# SCH_8_MCP23017_IC_SS_2021-10-13.net
KiCad netlist of a schematic drawn in EasyEDA
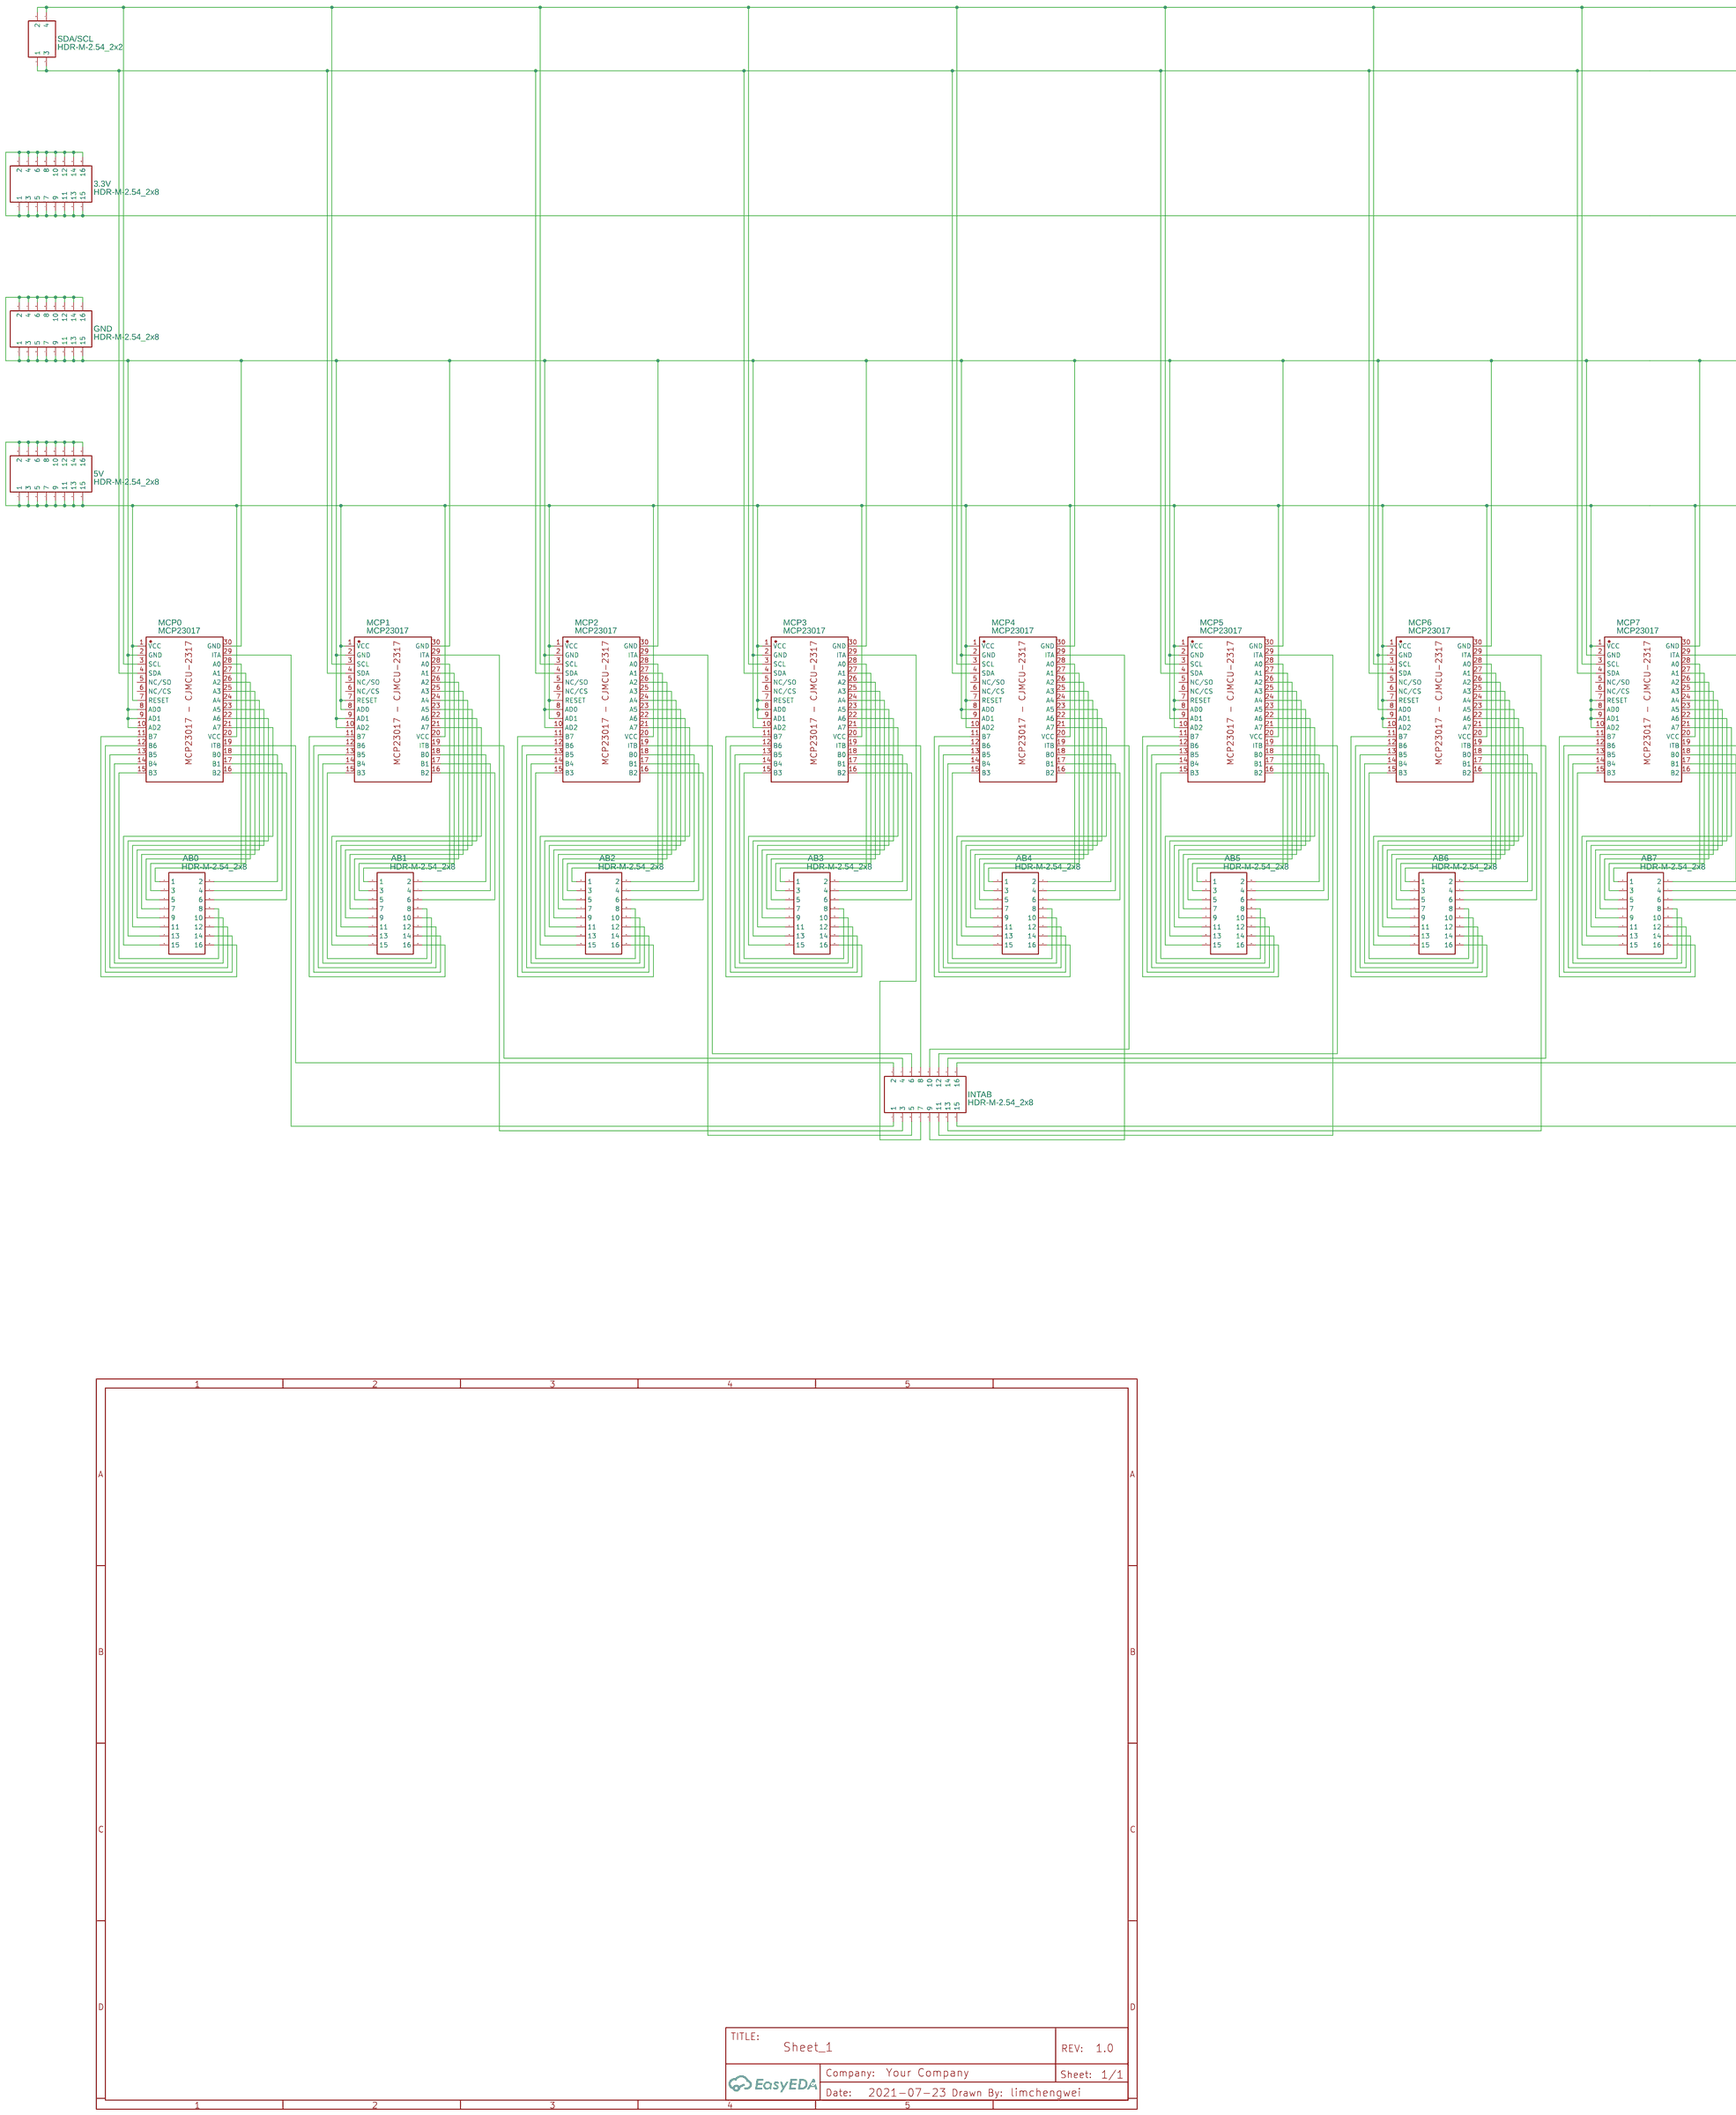
[diagram p0: schematic sheet]

(export (version "E")
  (design (tool "Eeschema 10.0.6"))
  (components
    (comp (ref "3.3V")
      (value "HDR-M-2.54_2x8")
      (fields (field (name "BOM_Supplier Part") "C68234"))
      (libsource (lib "") (part "HDR-M-2.54_2x8_2"))
    )
    (comp (ref "5V")
      (value "HDR-M-2.54_2x8")
      (fields (field (name "BOM_Supplier Part") "C68234"))
      (libsource (lib "") (part "HDR-M-2.54_2x8_3"))
    )
    (comp (ref "AB0")
      (value "HDR-M-2.54_2x8")
      (fields (field (name "BOM_Supplier Part") "C68234"))
      (libsource (lib "") (part "HDR-M-2.54_2x8"))
    )
    (comp (ref "AB1")
      (value "HDR-M-2.54_2x8")
      (fields (field (name "BOM_Supplier Part") "C68234"))
      (libsource (lib "") (part "HDR-M-2.54_2x8"))
    )
    (comp (ref "AB2")
      (value "HDR-M-2.54_2x8")
      (fields (field (name "BOM_Supplier Part") "C68234"))
      (libsource (lib "") (part "HDR-M-2.54_2x8"))
    )
    (comp (ref "AB3")
      (value "HDR-M-2.54_2x8")
      (fields (field (name "BOM_Supplier Part") "C68234"))
      (libsource (lib "") (part "HDR-M-2.54_2x8"))
    )
    (comp (ref "AB4")
      (value "HDR-M-2.54_2x8")
      (fields (field (name "BOM_Supplier Part") "C68234"))
      (libsource (lib "") (part "HDR-M-2.54_2x8"))
    )
    (comp (ref "AB5")
      (value "HDR-M-2.54_2x8")
      (fields (field (name "BOM_Supplier Part") "C68234"))
      (libsource (lib "") (part "HDR-M-2.54_2x8"))
    )
    (comp (ref "AB6")
      (value "HDR-M-2.54_2x8")
      (fields (field (name "BOM_Supplier Part") "C68234"))
      (libsource (lib "") (part "HDR-M-2.54_2x8"))
    )
    (comp (ref "AB7")
      (value "HDR-M-2.54_2x8")
      (fields (field (name "BOM_Supplier Part") "C68234"))
      (libsource (lib "") (part "HDR-M-2.54_2x8"))
    )
    (comp (ref "GND")
      (value "HDR-M-2.54_2x8")
      (fields (field (name "BOM_Supplier Part") "C68234"))
      (libsource (lib "") (part "HDR-M-2.54_2x8_4"))
    )
    (comp (ref "INTAB")
      (value "HDR-M-2.54_2x8")
      (fields (field (name "BOM_Supplier Part") "C68234"))
      (libsource (lib "") (part "HDR-M-2.54_2x8_1"))
    )
    (comp (ref "MCP0") (value "MCP23017") (libsource (lib "") (part "MCP23017")))
    (comp (ref "MCP1") (value "MCP23017") (libsource (lib "") (part "MCP23017")))
    (comp (ref "MCP2") (value "MCP23017") (libsource (lib "") (part "MCP23017")))
    (comp (ref "MCP3") (value "MCP23017") (libsource (lib "") (part "MCP23017")))
    (comp (ref "MCP4") (value "MCP23017") (libsource (lib "") (part "MCP23017")))
    (comp (ref "MCP5") (value "MCP23017") (libsource (lib "") (part "MCP23017")))
    (comp (ref "MCP6") (value "MCP23017") (libsource (lib "") (part "MCP23017")))
    (comp (ref "MCP7") (value "MCP23017") (libsource (lib "") (part "MCP23017")))
    (comp (ref "SDA/SCL")
      (value "HDR-M-2.54_2x2")
      (fields (field (name "BOM_Supplier Part") "C66690"))
      (libsource (lib "") (part "HDR-M-2.54_2x2"))
    )
  )
  (nets
    (net (code "1") (name "Net-(3.3V-Pad1)") (class "Default")
      (node (ref "3.3V") (pin "1") (pinfunction "1_1") (pintype "input"))
      (node (ref "3.3V") (pin "10") (pinfunction "10_10") (pintype "input"))
      (node (ref "3.3V") (pin "11") (pinfunction "11_11") (pintype "input"))
      (node (ref "3.3V") (pin "12") (pinfunction "12_12") (pintype "input"))
      (node (ref "3.3V") (pin "13") (pinfunction "13_13") (pintype "input"))
      (node (ref "3.3V") (pin "14") (pinfunction "14_14") (pintype "input"))
      (node (ref "3.3V") (pin "15") (pinfunction "15_15") (pintype "input"))
      (node (ref "3.3V") (pin "16") (pinfunction "16_16") (pintype "input"))
      (node (ref "3.3V") (pin "2") (pinfunction "2_2") (pintype "input"))
      (node (ref "3.3V") (pin "3") (pinfunction "3_3") (pintype "input"))
      (node (ref "3.3V") (pin "4") (pinfunction "4_4") (pintype "input"))
      (node (ref "3.3V") (pin "5") (pinfunction "5_5") (pintype "input"))
      (node (ref "3.3V") (pin "6") (pinfunction "6_6") (pintype "input"))
      (node (ref "3.3V") (pin "7") (pinfunction "7_7") (pintype "input"))
      (node (ref "3.3V") (pin "8") (pinfunction "8_8") (pintype "input"))
      (node (ref "3.3V") (pin "9") (pinfunction "9_9") (pintype "input"))
    )
    (net (code "2") (name "Net-(MCP0-A0)") (class "Default")
      (node (ref "AB0") (pin "1") (pinfunction "1_1") (pintype "input"))
      (node (ref "MCP0") (pin "28") (pinfunction "A0_28") (pintype "unspecified"))
    )
    (net (code "3") (name "Net-(MCP0-A1)") (class "Default")
      (node (ref "AB0") (pin "3") (pinfunction "3_3") (pintype "input"))
      (node (ref "MCP0") (pin "27") (pinfunction "A1_27") (pintype "unspecified"))
    )
    (net (code "4") (name "Net-(MCP0-A2)") (class "Default")
      (node (ref "AB0") (pin "5") (pinfunction "5_5") (pintype "input"))
      (node (ref "MCP0") (pin "26") (pinfunction "A2_26") (pintype "unspecified"))
    )
    (net (code "5") (name "Net-(MCP0-A3)") (class "Default")
      (node (ref "AB0") (pin "7") (pinfunction "7_7") (pintype "input"))
      (node (ref "MCP0") (pin "25") (pinfunction "A3_25") (pintype "unspecified"))
    )
    (net (code "6") (name "Net-(MCP0-A4)") (class "Default")
      (node (ref "AB0") (pin "9") (pinfunction "9_9") (pintype "input"))
      (node (ref "MCP0") (pin "24") (pinfunction "A4_24") (pintype "unspecified"))
    )
    (net (code "7") (name "Net-(MCP0-A5)") (class "Default")
      (node (ref "AB0") (pin "11") (pinfunction "11_11") (pintype "input"))
      (node (ref "MCP0") (pin "23") (pinfunction "A5_23") (pintype "unspecified"))
    )
    (net (code "8") (name "Net-(MCP0-A6)") (class "Default")
      (node (ref "AB0") (pin "13") (pinfunction "13_13") (pintype "input"))
      (node (ref "MCP0") (pin "22") (pinfunction "A6_22") (pintype "unspecified"))
    )
    (net (code "9") (name "Net-(MCP0-A7)") (class "Default")
      (node (ref "AB0") (pin "15") (pinfunction "15_15") (pintype "input"))
      (node (ref "MCP0") (pin "21") (pinfunction "A7_21") (pintype "unspecified"))
    )
    (net (code "10") (name "Net-(MCP0-AD0)") (class "Default")
      (node (ref "GND") (pin "1") (pinfunction "1_1") (pintype "input"))
      (node (ref "GND") (pin "10") (pinfunction "10_10") (pintype "input"))
      (node (ref "GND") (pin "11") (pinfunction "11_11") (pintype "input"))
      (node (ref "GND") (pin "12") (pinfunction "12_12") (pintype "input"))
      (node (ref "GND") (pin "13") (pinfunction "13_13") (pintype "input"))
      (node (ref "GND") (pin "14") (pinfunction "14_14") (pintype "input"))
      (node (ref "GND") (pin "15") (pinfunction "15_15") (pintype "input"))
      (node (ref "GND") (pin "16") (pinfunction "16_16") (pintype "input"))
      (node (ref "GND") (pin "2") (pinfunction "2_2") (pintype "input"))
      (node (ref "GND") (pin "3") (pinfunction "3_3") (pintype "input"))
      (node (ref "GND") (pin "4") (pinfunction "4_4") (pintype "input"))
      (node (ref "GND") (pin "5") (pinfunction "5_5") (pintype "input"))
      (node (ref "GND") (pin "6") (pinfunction "6_6") (pintype "input"))
      (node (ref "GND") (pin "7") (pinfunction "7_7") (pintype "input"))
      (node (ref "GND") (pin "8") (pinfunction "8_8") (pintype "input"))
      (node (ref "GND") (pin "9") (pinfunction "9_9") (pintype "input"))
      (node (ref "MCP0") (pin "10") (pinfunction "AD2_10") (pintype "unspecified"))
      (node (ref "MCP0") (pin "2") (pinfunction "GND_2") (pintype "passive"))
      (node (ref "MCP0") (pin "30") (pinfunction "GND_30") (pintype "passive"))
      (node (ref "MCP0") (pin "8") (pinfunction "AD0_8") (pintype "unspecified"))
      (node (ref "MCP0") (pin "9") (pinfunction "AD1_9") (pintype "unspecified"))
      (node (ref "MCP1") (pin "10") (pinfunction "AD2_10") (pintype "unspecified"))
      (node (ref "MCP1") (pin "2") (pinfunction "GND_2") (pintype "passive"))
      (node (ref "MCP1") (pin "30") (pinfunction "GND_30") (pintype "passive"))
      (node (ref "MCP1") (pin "9") (pinfunction "AD1_9") (pintype "unspecified"))
      (node (ref "MCP2") (pin "10") (pinfunction "AD2_10") (pintype "unspecified"))
      (node (ref "MCP2") (pin "2") (pinfunction "GND_2") (pintype "passive"))
      (node (ref "MCP2") (pin "30") (pinfunction "GND_30") (pintype "passive"))
      (node (ref "MCP2") (pin "8") (pinfunction "AD0_8") (pintype "unspecified"))
      (node (ref "MCP3") (pin "10") (pinfunction "AD2_10") (pintype "unspecified"))
      (node (ref "MCP3") (pin "2") (pinfunction "GND_2") (pintype "passive"))
      (node (ref "MCP3") (pin "30") (pinfunction "GND_30") (pintype "passive"))
      (node (ref "MCP4") (pin "2") (pinfunction "GND_2") (pintype "passive"))
      (node (ref "MCP4") (pin "30") (pinfunction "GND_30") (pintype "passive"))
      (node (ref "MCP4") (pin "8") (pinfunction "AD0_8") (pintype "unspecified"))
      (node (ref "MCP4") (pin "9") (pinfunction "AD1_9") (pintype "unspecified"))
      (node (ref "MCP5") (pin "2") (pinfunction "GND_2") (pintype "passive"))
      (node (ref "MCP5") (pin "30") (pinfunction "GND_30") (pintype "passive"))
      (node (ref "MCP5") (pin "9") (pinfunction "AD1_9") (pintype "unspecified"))
      (node (ref "MCP6") (pin "2") (pinfunction "GND_2") (pintype "passive"))
      (node (ref "MCP6") (pin "30") (pinfunction "GND_30") (pintype "passive"))
      (node (ref "MCP6") (pin "8") (pinfunction "AD0_8") (pintype "unspecified"))
      (node (ref "MCP7") (pin "2") (pinfunction "GND_2") (pintype "passive"))
      (node (ref "MCP7") (pin "30") (pinfunction "GND_30") (pintype "passive"))
    )
    (net (code "11") (name "Net-(MCP0-B0)") (class "Default")
      (node (ref "AB0") (pin "2") (pinfunction "2_2") (pintype "input"))
      (node (ref "MCP0") (pin "18") (pinfunction "B0_18") (pintype "unspecified"))
    )
    (net (code "12") (name "Net-(MCP0-B1)") (class "Default")
      (node (ref "AB0") (pin "4") (pinfunction "4_4") (pintype "input"))
      (node (ref "MCP0") (pin "17") (pinfunction "B1_17") (pintype "unspecified"))
    )
    (net (code "13") (name "Net-(MCP0-B2)") (class "Default")
      (node (ref "AB0") (pin "6") (pinfunction "6_6") (pintype "input"))
      (node (ref "MCP0") (pin "16") (pinfunction "B2_16") (pintype "unspecified"))
    )
    (net (code "14") (name "Net-(MCP0-B3)") (class "Default")
      (node (ref "AB0") (pin "8") (pinfunction "8_8") (pintype "input"))
      (node (ref "MCP0") (pin "15") (pinfunction "B3_15") (pintype "unspecified"))
    )
    (net (code "15") (name "Net-(MCP0-B4)") (class "Default")
      (node (ref "AB0") (pin "10") (pinfunction "10_10") (pintype "input"))
      (node (ref "MCP0") (pin "14") (pinfunction "B4_14") (pintype "unspecified"))
    )
    (net (code "16") (name "Net-(MCP0-B5)") (class "Default")
      (node (ref "AB0") (pin "12") (pinfunction "12_12") (pintype "input"))
      (node (ref "MCP0") (pin "13") (pinfunction "B5_13") (pintype "unspecified"))
    )
    (net (code "17") (name "Net-(MCP0-B6)") (class "Default")
      (node (ref "AB0") (pin "14") (pinfunction "14_14") (pintype "input"))
      (node (ref "MCP0") (pin "12") (pinfunction "B6_12") (pintype "unspecified"))
    )
    (net (code "18") (name "Net-(MCP0-B7)") (class "Default")
      (node (ref "AB0") (pin "16") (pinfunction "16_16") (pintype "input"))
      (node (ref "MCP0") (pin "11") (pinfunction "B7_11") (pintype "unspecified"))
    )
    (net (code "19") (name "Net-(MCP0-ITA)") (class "Default")
      (node (ref "INTAB") (pin "1") (pinfunction "1_1") (pintype "input"))
      (node (ref "MCP0") (pin "29") (pinfunction "ITA_29") (pintype "unspecified"))
    )
    (net (code "20") (name "Net-(MCP0-ITB)") (class "Default")
      (node (ref "INTAB") (pin "2") (pinfunction "2_2") (pintype "input"))
      (node (ref "MCP0") (pin "19") (pinfunction "ITB_19") (pintype "unspecified"))
    )
    (net (code "21") (name "Net-(MCP0-RESET)") (class "Default")
      (node (ref "5V") (pin "1") (pinfunction "1_1") (pintype "input"))
      (node (ref "5V") (pin "10") (pinfunction "10_10") (pintype "input"))
      (node (ref "5V") (pin "11") (pinfunction "11_11") (pintype "input"))
      (node (ref "5V") (pin "12") (pinfunction "12_12") (pintype "input"))
      (node (ref "5V") (pin "13") (pinfunction "13_13") (pintype "input"))
      (node (ref "5V") (pin "14") (pinfunction "14_14") (pintype "input"))
      (node (ref "5V") (pin "15") (pinfunction "15_15") (pintype "input"))
      (node (ref "5V") (pin "16") (pinfunction "16_16") (pintype "input"))
      (node (ref "5V") (pin "2") (pinfunction "2_2") (pintype "input"))
      (node (ref "5V") (pin "3") (pinfunction "3_3") (pintype "input"))
      (node (ref "5V") (pin "4") (pinfunction "4_4") (pintype "input"))
      (node (ref "5V") (pin "5") (pinfunction "5_5") (pintype "input"))
      (node (ref "5V") (pin "6") (pinfunction "6_6") (pintype "input"))
      (node (ref "5V") (pin "7") (pinfunction "7_7") (pintype "input"))
      (node (ref "5V") (pin "8") (pinfunction "8_8") (pintype "input"))
      (node (ref "5V") (pin "9") (pinfunction "9_9") (pintype "input"))
      (node (ref "MCP0") (pin "1") (pinfunction "VCC_1") (pintype "passive"))
      (node (ref "MCP0") (pin "20") (pinfunction "VCC_20") (pintype "passive"))
      (node (ref "MCP0") (pin "7") (pinfunction "RESET_7") (pintype "input"))
      (node (ref "MCP1") (pin "1") (pinfunction "VCC_1") (pintype "passive"))
      (node (ref "MCP1") (pin "20") (pinfunction "VCC_20") (pintype "passive"))
      (node (ref "MCP1") (pin "7") (pinfunction "RESET_7") (pintype "input"))
      (node (ref "MCP1") (pin "8") (pinfunction "AD0_8") (pintype "unspecified"))
      (node (ref "MCP2") (pin "1") (pinfunction "VCC_1") (pintype "passive"))
      (node (ref "MCP2") (pin "20") (pinfunction "VCC_20") (pintype "passive"))
      (node (ref "MCP2") (pin "7") (pinfunction "RESET_7") (pintype "input"))
      (node (ref "MCP2") (pin "9") (pinfunction "AD1_9") (pintype "unspecified"))
      (node (ref "MCP3") (pin "1") (pinfunction "VCC_1") (pintype "passive"))
      (node (ref "MCP3") (pin "20") (pinfunction "VCC_20") (pintype "passive"))
      (node (ref "MCP3") (pin "7") (pinfunction "RESET_7") (pintype "input"))
      (node (ref "MCP3") (pin "8") (pinfunction "AD0_8") (pintype "unspecified"))
      (node (ref "MCP3") (pin "9") (pinfunction "AD1_9") (pintype "unspecified"))
      (node (ref "MCP4") (pin "1") (pinfunction "VCC_1") (pintype "passive"))
      (node (ref "MCP4") (pin "10") (pinfunction "AD2_10") (pintype "unspecified"))
      (node (ref "MCP4") (pin "20") (pinfunction "VCC_20") (pintype "passive"))
      (node (ref "MCP4") (pin "7") (pinfunction "RESET_7") (pintype "input"))
      (node (ref "MCP5") (pin "1") (pinfunction "VCC_1") (pintype "passive"))
      (node (ref "MCP5") (pin "10") (pinfunction "AD2_10") (pintype "unspecified"))
      (node (ref "MCP5") (pin "20") (pinfunction "VCC_20") (pintype "passive"))
      (node (ref "MCP5") (pin "7") (pinfunction "RESET_7") (pintype "input"))
      (node (ref "MCP5") (pin "8") (pinfunction "AD0_8") (pintype "unspecified"))
      (node (ref "MCP6") (pin "1") (pinfunction "VCC_1") (pintype "passive"))
      (node (ref "MCP6") (pin "10") (pinfunction "AD2_10") (pintype "unspecified"))
      (node (ref "MCP6") (pin "20") (pinfunction "VCC_20") (pintype "passive"))
      (node (ref "MCP6") (pin "7") (pinfunction "RESET_7") (pintype "input"))
      (node (ref "MCP6") (pin "9") (pinfunction "AD1_9") (pintype "unspecified"))
      (node (ref "MCP7") (pin "1") (pinfunction "VCC_1") (pintype "passive"))
      (node (ref "MCP7") (pin "10") (pinfunction "AD2_10") (pintype "unspecified"))
      (node (ref "MCP7") (pin "20") (pinfunction "VCC_20") (pintype "passive"))
      (node (ref "MCP7") (pin "7") (pinfunction "RESET_7") (pintype "input"))
      (node (ref "MCP7") (pin "8") (pinfunction "AD0_8") (pintype "unspecified"))
      (node (ref "MCP7") (pin "9") (pinfunction "AD1_9") (pintype "unspecified"))
    )
    (net (code "22") (name "Net-(MCP0-SCL)") (class "Default")
      (node (ref "MCP0") (pin "3") (pinfunction "SCL_3") (pintype "bidirectional"))
      (node (ref "MCP1") (pin "3") (pinfunction "SCL_3") (pintype "bidirectional"))
      (node (ref "MCP2") (pin "3") (pinfunction "SCL_3") (pintype "bidirectional"))
      (node (ref "MCP3") (pin "3") (pinfunction "SCL_3") (pintype "bidirectional"))
      (node (ref "MCP4") (pin "3") (pinfunction "SCL_3") (pintype "bidirectional"))
      (node (ref "MCP5") (pin "3") (pinfunction "SCL_3") (pintype "bidirectional"))
      (node (ref "MCP6") (pin "3") (pinfunction "SCL_3") (pintype "bidirectional"))
      (node (ref "MCP7") (pin "3") (pinfunction "SCL_3") (pintype "bidirectional"))
      (node (ref "SDA/SCL") (pin "2") (pinfunction "2_2") (pintype "input"))
      (node (ref "SDA/SCL") (pin "4") (pinfunction "4_4") (pintype "input"))
    )
    (net (code "23") (name "Net-(MCP0-SDA)") (class "Default")
      (node (ref "MCP0") (pin "4") (pinfunction "SDA_4") (pintype "bidirectional"))
      (node (ref "MCP1") (pin "4") (pinfunction "SDA_4") (pintype "bidirectional"))
      (node (ref "MCP2") (pin "4") (pinfunction "SDA_4") (pintype "bidirectional"))
      (node (ref "MCP3") (pin "4") (pinfunction "SDA_4") (pintype "bidirectional"))
      (node (ref "MCP4") (pin "4") (pinfunction "SDA_4") (pintype "bidirectional"))
      (node (ref "MCP5") (pin "4") (pinfunction "SDA_4") (pintype "bidirectional"))
      (node (ref "MCP6") (pin "4") (pinfunction "SDA_4") (pintype "bidirectional"))
      (node (ref "MCP7") (pin "4") (pinfunction "SDA_4") (pintype "bidirectional"))
      (node (ref "SDA/SCL") (pin "1") (pinfunction "1_1") (pintype "input"))
      (node (ref "SDA/SCL") (pin "3") (pinfunction "3_3") (pintype "input"))
    )
    (net (code "24") (name "Net-(MCP1-A0)") (class "Default")
      (node (ref "AB1") (pin "1") (pinfunction "1_1") (pintype "input"))
      (node (ref "MCP1") (pin "28") (pinfunction "A0_28") (pintype "unspecified"))
    )
    (net (code "25") (name "Net-(MCP1-A1)") (class "Default")
      (node (ref "AB1") (pin "3") (pinfunction "3_3") (pintype "input"))
      (node (ref "MCP1") (pin "27") (pinfunction "A1_27") (pintype "unspecified"))
    )
    (net (code "26") (name "Net-(MCP1-A2)") (class "Default")
      (node (ref "AB1") (pin "5") (pinfunction "5_5") (pintype "input"))
      (node (ref "MCP1") (pin "26") (pinfunction "A2_26") (pintype "unspecified"))
    )
    (net (code "27") (name "Net-(MCP1-A3)") (class "Default")
      (node (ref "AB1") (pin "7") (pinfunction "7_7") (pintype "input"))
      (node (ref "MCP1") (pin "25") (pinfunction "A3_25") (pintype "unspecified"))
    )
    (net (code "28") (name "Net-(MCP1-A4)") (class "Default")
      (node (ref "AB1") (pin "9") (pinfunction "9_9") (pintype "input"))
      (node (ref "MCP1") (pin "24") (pinfunction "A4_24") (pintype "unspecified"))
    )
    (net (code "29") (name "Net-(MCP1-A5)") (class "Default")
      (node (ref "AB1") (pin "11") (pinfunction "11_11") (pintype "input"))
      (node (ref "MCP1") (pin "23") (pinfunction "A5_23") (pintype "unspecified"))
    )
    (net (code "30") (name "Net-(MCP1-A6)") (class "Default")
      (node (ref "AB1") (pin "13") (pinfunction "13_13") (pintype "input"))
      (node (ref "MCP1") (pin "22") (pinfunction "A6_22") (pintype "unspecified"))
    )
    (net (code "31") (name "Net-(MCP1-A7)") (class "Default")
      (node (ref "AB1") (pin "15") (pinfunction "15_15") (pintype "input"))
      (node (ref "MCP1") (pin "21") (pinfunction "A7_21") (pintype "unspecified"))
    )
    (net (code "32") (name "Net-(MCP1-B0)") (class "Default")
      (node (ref "AB1") (pin "2") (pinfunction "2_2") (pintype "input"))
      (node (ref "MCP1") (pin "18") (pinfunction "B0_18") (pintype "unspecified"))
    )
    (net (code "33") (name "Net-(MCP1-B1)") (class "Default")
      (node (ref "AB1") (pin "4") (pinfunction "4_4") (pintype "input"))
      (node (ref "MCP1") (pin "17") (pinfunction "B1_17") (pintype "unspecified"))
    )
    (net (code "34") (name "Net-(MCP1-B2)") (class "Default")
      (node (ref "AB1") (pin "6") (pinfunction "6_6") (pintype "input"))
      (node (ref "MCP1") (pin "16") (pinfunction "B2_16") (pintype "unspecified"))
    )
    (net (code "35") (name "Net-(MCP1-B3)") (class "Default")
      (node (ref "AB1") (pin "8") (pinfunction "8_8") (pintype "input"))
      (node (ref "MCP1") (pin "15") (pinfunction "B3_15") (pintype "unspecified"))
    )
    (net (code "36") (name "Net-(MCP1-B4)") (class "Default")
      (node (ref "AB1") (pin "10") (pinfunction "10_10") (pintype "input"))
      (node (ref "MCP1") (pin "14") (pinfunction "B4_14") (pintype "unspecified"))
    )
    (net (code "37") (name "Net-(MCP1-B5)") (class "Default")
      (node (ref "AB1") (pin "12") (pinfunction "12_12") (pintype "input"))
      (node (ref "MCP1") (pin "13") (pinfunction "B5_13") (pintype "unspecified"))
    )
    (net (code "38") (name "Net-(MCP1-B6)") (class "Default")
      (node (ref "AB1") (pin "14") (pinfunction "14_14") (pintype "input"))
      (node (ref "MCP1") (pin "12") (pinfunction "B6_12") (pintype "unspecified"))
    )
    (net (code "39") (name "Net-(MCP1-B7)") (class "Default")
      (node (ref "AB1") (pin "16") (pinfunction "16_16") (pintype "input"))
      (node (ref "MCP1") (pin "11") (pinfunction "B7_11") (pintype "unspecified"))
    )
    (net (code "40") (name "Net-(MCP1-ITA)") (class "Default")
      (node (ref "INTAB") (pin "3") (pinfunction "3_3") (pintype "input"))
      (node (ref "MCP1") (pin "29") (pinfunction "ITA_29") (pintype "unspecified"))
    )
    (net (code "41") (name "Net-(MCP1-ITB)") (class "Default")
      (node (ref "INTAB") (pin "4") (pinfunction "4_4") (pintype "input"))
      (node (ref "MCP1") (pin "19") (pinfunction "ITB_19") (pintype "unspecified"))
    )
    (net (code "42") (name "Net-(MCP2-A0)") (class "Default")
      (node (ref "AB2") (pin "1") (pinfunction "1_1") (pintype "input"))
      (node (ref "MCP2") (pin "28") (pinfunction "A0_28") (pintype "unspecified"))
    )
    (net (code "43") (name "Net-(MCP2-A1)") (class "Default")
      (node (ref "AB2") (pin "3") (pinfunction "3_3") (pintype "input"))
      (node (ref "MCP2") (pin "27") (pinfunction "A1_27") (pintype "unspecified"))
    )
    (net (code "44") (name "Net-(MCP2-A2)") (class "Default")
      (node (ref "AB2") (pin "5") (pinfunction "5_5") (pintype "input"))
      (node (ref "MCP2") (pin "26") (pinfunction "A2_26") (pintype "unspecified"))
    )
    (net (code "45") (name "Net-(MCP2-A3)") (class "Default")
      (node (ref "AB2") (pin "7") (pinfunction "7_7") (pintype "input"))
      (node (ref "MCP2") (pin "25") (pinfunction "A3_25") (pintype "unspecified"))
    )
    (net (code "46") (name "Net-(MCP2-A4)") (class "Default")
      (node (ref "AB2") (pin "9") (pinfunction "9_9") (pintype "input"))
      (node (ref "MCP2") (pin "24") (pinfunction "A4_24") (pintype "unspecified"))
    )
    (net (code "47") (name "Net-(MCP2-A5)") (class "Default")
      (node (ref "AB2") (pin "11") (pinfunction "11_11") (pintype "input"))
      (node (ref "MCP2") (pin "23") (pinfunction "A5_23") (pintype "unspecified"))
    )
    (net (code "48") (name "Net-(MCP2-A6)") (class "Default")
      (node (ref "AB2") (pin "13") (pinfunction "13_13") (pintype "input"))
      (node (ref "MCP2") (pin "22") (pinfunction "A6_22") (pintype "unspecified"))
    )
    (net (code "49") (name "Net-(MCP2-A7)") (class "Default")
      (node (ref "AB2") (pin "15") (pinfunction "15_15") (pintype "input"))
      (node (ref "MCP2") (pin "21") (pinfunction "A7_21") (pintype "unspecified"))
    )
    (net (code "50") (name "Net-(MCP2-B0)") (class "Default")
      (node (ref "AB2") (pin "2") (pinfunction "2_2") (pintype "input"))
      (node (ref "MCP2") (pin "18") (pinfunction "B0_18") (pintype "unspecified"))
    )
    (net (code "51") (name "Net-(MCP2-B1)") (class "Default")
      (node (ref "AB2") (pin "4") (pinfunction "4_4") (pintype "input"))
      (node (ref "MCP2") (pin "17") (pinfunction "B1_17") (pintype "unspecified"))
    )
    (net (code "52") (name "Net-(MCP2-B2)") (class "Default")
      (node (ref "AB2") (pin "6") (pinfunction "6_6") (pintype "input"))
      (node (ref "MCP2") (pin "16") (pinfunction "B2_16") (pintype "unspecified"))
    )
    (net (code "53") (name "Net-(MCP2-B3)") (class "Default")
      (node (ref "AB2") (pin "8") (pinfunction "8_8") (pintype "input"))
      (node (ref "MCP2") (pin "15") (pinfunction "B3_15") (pintype "unspecified"))
    )
    (net (code "54") (name "Net-(MCP2-B4)") (class "Default")
      (node (ref "AB2") (pin "10") (pinfunction "10_10") (pintype "input"))
      (node (ref "MCP2") (pin "14") (pinfunction "B4_14") (pintype "unspecified"))
    )
    (net (code "55") (name "Net-(MCP2-B5)") (class "Default")
      (node (ref "AB2") (pin "12") (pinfunction "12_12") (pintype "input"))
      (node (ref "MCP2") (pin "13") (pinfunction "B5_13") (pintype "unspecified"))
    )
    (net (code "56") (name "Net-(MCP2-B6)") (class "Default")
      (node (ref "AB2") (pin "14") (pinfunction "14_14") (pintype "input"))
      (node (ref "MCP2") (pin "12") (pinfunction "B6_12") (pintype "unspecified"))
    )
    (net (code "57") (name "Net-(MCP2-B7)") (class "Default")
      (node (ref "AB2") (pin "16") (pinfunction "16_16") (pintype "input"))
      (node (ref "MCP2") (pin "11") (pinfunction "B7_11") (pintype "unspecified"))
    )
    (net (code "58") (name "Net-(MCP2-ITA)") (class "Default")
      (node (ref "INTAB") (pin "5") (pinfunction "5_5") (pintype "input"))
      (node (ref "MCP2") (pin "29") (pinfunction "ITA_29") (pintype "unspecified"))
    )
    (net (code "59") (name "Net-(MCP2-ITB)") (class "Default")
      (node (ref "INTAB") (pin "6") (pinfunction "6_6") (pintype "input"))
      (node (ref "MCP2") (pin "19") (pinfunction "ITB_19") (pintype "unspecified"))
    )
    (net (code "60") (name "Net-(MCP3-A0)") (class "Default")
      (node (ref "AB3") (pin "1") (pinfunction "1_1") (pintype "input"))
      (node (ref "MCP3") (pin "28") (pinfunction "A0_28") (pintype "unspecified"))
    )
    (net (code "61") (name "Net-(MCP3-A1)") (class "Default")
      (node (ref "AB3") (pin "3") (pinfunction "3_3") (pintype "input"))
      (node (ref "MCP3") (pin "27") (pinfunction "A1_27") (pintype "unspecified"))
    )
    (net (code "62") (name "Net-(MCP3-A2)") (class "Default")
      (node (ref "AB3") (pin "5") (pinfunction "5_5") (pintype "input"))
      (node (ref "MCP3") (pin "26") (pinfunction "A2_26") (pintype "unspecified"))
    )
    (net (code "63") (name "Net-(MCP3-A3)") (class "Default")
      (node (ref "AB3") (pin "7") (pinfunction "7_7") (pintype "input"))
      (node (ref "MCP3") (pin "25") (pinfunction "A3_25") (pintype "unspecified"))
    )
    (net (code "64") (name "Net-(MCP3-A4)") (class "Default")
      (node (ref "AB3") (pin "9") (pinfunction "9_9") (pintype "input"))
      (node (ref "MCP3") (pin "24") (pinfunction "A4_24") (pintype "unspecified"))
    )
    (net (code "65") (name "Net-(MCP3-A5)") (class "Default")
      (node (ref "AB3") (pin "11") (pinfunction "11_11") (pintype "input"))
      (node (ref "MCP3") (pin "23") (pinfunction "A5_23") (pintype "unspecified"))
    )
    (net (code "66") (name "Net-(MCP3-A6)") (class "Default")
      (node (ref "AB3") (pin "13") (pinfunction "13_13") (pintype "input"))
      (node (ref "MCP3") (pin "22") (pinfunction "A6_22") (pintype "unspecified"))
    )
    (net (code "67") (name "Net-(MCP3-A7)") (class "Default")
      (node (ref "AB3") (pin "15") (pinfunction "15_15") (pintype "input"))
      (node (ref "MCP3") (pin "21") (pinfunction "A7_21") (pintype "unspecified"))
    )
    (net (code "68") (name "Net-(MCP3-B0)") (class "Default")
      (node (ref "AB3") (pin "2") (pinfunction "2_2") (pintype "input"))
      (node (ref "MCP3") (pin "18") (pinfunction "B0_18") (pintype "unspecified"))
    )
    (net (code "69") (name "Net-(MCP3-B1)") (class "Default")
      (node (ref "AB3") (pin "4") (pinfunction "4_4") (pintype "input"))
      (node (ref "MCP3") (pin "17") (pinfunction "B1_17") (pintype "unspecified"))
    )
    (net (code "70") (name "Net-(MCP3-B2)") (class "Default")
      (node (ref "AB3") (pin "6") (pinfunction "6_6") (pintype "input"))
      (node (ref "MCP3") (pin "16") (pinfunction "B2_16") (pintype "unspecified"))
    )
    (net (code "71") (name "Net-(MCP3-B3)") (class "Default")
      (node (ref "AB3") (pin "8") (pinfunction "8_8") (pintype "input"))
      (node (ref "MCP3") (pin "15") (pinfunction "B3_15") (pintype "unspecified"))
    )
    (net (code "72") (name "Net-(MCP3-B4)") (class "Default")
      (node (ref "AB3") (pin "10") (pinfunction "10_10") (pintype "input"))
      (node (ref "MCP3") (pin "14") (pinfunction "B4_14") (pintype "unspecified"))
    )
    (net (code "73") (name "Net-(MCP3-B5)") (class "Default")
      (node (ref "AB3") (pin "12") (pinfunction "12_12") (pintype "input"))
      (node (ref "MCP3") (pin "13") (pinfunction "B5_13") (pintype "unspecified"))
    )
    (net (code "74") (name "Net-(MCP3-B6)") (class "Default")
      (node (ref "AB3") (pin "14") (pinfunction "14_14") (pintype "input"))
      (node (ref "MCP3") (pin "12") (pinfunction "B6_12") (pintype "unspecified"))
    )
    (net (code "75") (name "Net-(MCP3-B7)") (class "Default")
      (node (ref "AB3") (pin "16") (pinfunction "16_16") (pintype "input"))
      (node (ref "MCP3") (pin "11") (pinfunction "B7_11") (pintype "unspecified"))
    )
    (net (code "76") (name "Net-(MCP3-ITA)") (class "Default")
      (node (ref "INTAB") (pin "7") (pinfunction "7_7") (pintype "input"))
      (node (ref "MCP3") (pin "29") (pinfunction "ITA_29") (pintype "unspecified"))
    )
    (net (code "77") (name "Net-(MCP3-ITB)") (class "Default")
      (node (ref "INTAB") (pin "8") (pinfunction "8_8") (pintype "input"))
      (node (ref "MCP3") (pin "19") (pinfunction "ITB_19") (pintype "unspecified"))
    )
    (net (code "78") (name "Net-(MCP4-A0)") (class "Default")
      (node (ref "AB4") (pin "1") (pinfunction "1_1") (pintype "input"))
      (node (ref "MCP4") (pin "28") (pinfunction "A0_28") (pintype "unspecified"))
    )
    (net (code "79") (name "Net-(MCP4-A1)") (class "Default")
      (node (ref "AB4") (pin "3") (pinfunction "3_3") (pintype "input"))
      (node (ref "MCP4") (pin "27") (pinfunction "A1_27") (pintype "unspecified"))
    )
    (net (code "80") (name "Net-(MCP4-A2)") (class "Default")
      (node (ref "AB4") (pin "5") (pinfunction "5_5") (pintype "input"))
      (node (ref "MCP4") (pin "26") (pinfunction "A2_26") (pintype "unspecified"))
    )
    (net (code "81") (name "Net-(MCP4-A3)") (class "Default")
      (node (ref "AB4") (pin "7") (pinfunction "7_7") (pintype "input"))
      (node (ref "MCP4") (pin "25") (pinfunction "A3_25") (pintype "unspecified"))
    )
    (net (code "82") (name "Net-(MCP4-A4)") (class "Default")
      (node (ref "AB4") (pin "9") (pinfunction "9_9") (pintype "input"))
      (node (ref "MCP4") (pin "24") (pinfunction "A4_24") (pintype "unspecified"))
    )
    (net (code "83") (name "Net-(MCP4-A5)") (class "Default")
      (node (ref "AB4") (pin "11") (pinfunction "11_11") (pintype "input"))
      (node (ref "MCP4") (pin "23") (pinfunction "A5_23") (pintype "unspecified"))
    )
    (net (code "84") (name "Net-(MCP4-A6)") (class "Default")
      (node (ref "AB4") (pin "13") (pinfunction "13_13") (pintype "input"))
      (node (ref "MCP4") (pin "22") (pinfunction "A6_22") (pintype "unspecified"))
    )
    (net (code "85") (name "Net-(MCP4-A7)") (class "Default")
      (node (ref "AB4") (pin "15") (pinfunction "15_15") (pintype "input"))
      (node (ref "MCP4") (pin "21") (pinfunction "A7_21") (pintype "unspecified"))
    )
    (net (code "86") (name "Net-(MCP4-B0)") (class "Default")
      (node (ref "AB4") (pin "2") (pinfunction "2_2") (pintype "input"))
      (node (ref "MCP4") (pin "18") (pinfunction "B0_18") (pintype "unspecified"))
    )
    (net (code "87") (name "Net-(MCP4-B1)") (class "Default")
      (node (ref "AB4") (pin "4") (pinfunction "4_4") (pintype "input"))
      (node (ref "MCP4") (pin "17") (pinfunction "B1_17") (pintype "unspecified"))
    )
    (net (code "88") (name "Net-(MCP4-B2)") (class "Default")
      (node (ref "AB4") (pin "6") (pinfunction "6_6") (pintype "input"))
      (node (ref "MCP4") (pin "16") (pinfunction "B2_16") (pintype "unspecified"))
    )
    (net (code "89") (name "Net-(MCP4-B3)") (class "Default")
      (node (ref "AB4") (pin "8") (pinfunction "8_8") (pintype "input"))
      (node (ref "MCP4") (pin "15") (pinfunction "B3_15") (pintype "unspecified"))
    )
    (net (code "90") (name "Net-(MCP4-B4)") (class "Default")
      (node (ref "AB4") (pin "10") (pinfunction "10_10") (pintype "input"))
      (node (ref "MCP4") (pin "14") (pinfunction "B4_14") (pintype "unspecified"))
    )
    (net (code "91") (name "Net-(MCP4-B5)") (class "Default")
      (node (ref "AB4") (pin "12") (pinfunction "12_12") (pintype "input"))
      (node (ref "MCP4") (pin "13") (pinfunction "B5_13") (pintype "unspecified"))
    )
    (net (code "92") (name "Net-(MCP4-B6)") (class "Default")
      (node (ref "AB4") (pin "14") (pinfunction "14_14") (pintype "input"))
      (node (ref "MCP4") (pin "12") (pinfunction "B6_12") (pintype "unspecified"))
    )
    (net (code "93") (name "Net-(MCP4-B7)") (class "Default")
      (node (ref "AB4") (pin "16") (pinfunction "16_16") (pintype "input"))
      (node (ref "MCP4") (pin "11") (pinfunction "B7_11") (pintype "unspecified"))
    )
    (net (code "94") (name "Net-(MCP4-ITA)") (class "Default")
      (node (ref "INTAB") (pin "9") (pinfunction "9_9") (pintype "input"))
      (node (ref "MCP4") (pin "29") (pinfunction "ITA_29") (pintype "unspecified"))
    )
    (net (code "95") (name "Net-(MCP4-ITB)") (class "Default")
      (node (ref "INTAB") (pin "10") (pinfunction "10_10") (pintype "input"))
      (node (ref "MCP4") (pin "19") (pinfunction "ITB_19") (pintype "unspecified"))
    )
    (net (code "96") (name "Net-(MCP5-A0)") (class "Default")
      (node (ref "AB5") (pin "1") (pinfunction "1_1") (pintype "input"))
      (node (ref "MCP5") (pin "28") (pinfunction "A0_28") (pintype "unspecified"))
    )
    (net (code "97") (name "Net-(MCP5-A1)") (class "Default")
      (node (ref "AB5") (pin "3") (pinfunction "3_3") (pintype "input"))
      (node (ref "MCP5") (pin "27") (pinfunction "A1_27") (pintype "unspecified"))
    )
    (net (code "98") (name "Net-(MCP5-A2)") (class "Default")
      (node (ref "AB5") (pin "5") (pinfunction "5_5") (pintype "input"))
      (node (ref "MCP5") (pin "26") (pinfunction "A2_26") (pintype "unspecified"))
    )
    (net (code "99") (name "Net-(MCP5-A3)") (class "Default")
      (node (ref "AB5") (pin "7") (pinfunction "7_7") (pintype "input"))
      (node (ref "MCP5") (pin "25") (pinfunction "A3_25") (pintype "unspecified"))
    )
    (net (code "100") (name "Net-(MCP5-A4)") (class "Default")
      (node (ref "AB5") (pin "9") (pinfunction "9_9") (pintype "input"))
      (node (ref "MCP5") (pin "24") (pinfunction "A4_24") (pintype "unspecified"))
    )
    (net (code "101") (name "Net-(MCP5-A5)") (class "Default")
      (node (ref "AB5") (pin "11") (pinfunction "11_11") (pintype "input"))
      (node (ref "MCP5") (pin "23") (pinfunction "A5_23") (pintype "unspecified"))
    )
    (net (code "102") (name "Net-(MCP5-A6)") (class "Default")
      (node (ref "AB5") (pin "13") (pinfunction "13_13") (pintype "input"))
      (node (ref "MCP5") (pin "22") (pinfunction "A6_22") (pintype "unspecified"))
    )
    (net (code "103") (name "Net-(MCP5-A7)") (class "Default")
      (node (ref "AB5") (pin "15") (pinfunction "15_15") (pintype "input"))
      (node (ref "MCP5") (pin "21") (pinfunction "A7_21") (pintype "unspecified"))
    )
    (net (code "104") (name "Net-(MCP5-B0)") (class "Default")
      (node (ref "AB5") (pin "2") (pinfunction "2_2") (pintype "input"))
      (node (ref "MCP5") (pin "18") (pinfunction "B0_18") (pintype "unspecified"))
    )
    (net (code "105") (name "Net-(MCP5-B1)") (class "Default")
      (node (ref "AB5") (pin "4") (pinfunction "4_4") (pintype "input"))
      (node (ref "MCP5") (pin "17") (pinfunction "B1_17") (pintype "unspecified"))
    )
    (net (code "106") (name "Net-(MCP5-B2)") (class "Default")
      (node (ref "AB5") (pin "6") (pinfunction "6_6") (pintype "input"))
      (node (ref "MCP5") (pin "16") (pinfunction "B2_16") (pintype "unspecified"))
    )
    (net (code "107") (name "Net-(MCP5-B3)") (class "Default")
      (node (ref "AB5") (pin "8") (pinfunction "8_8") (pintype "input"))
      (node (ref "MCP5") (pin "15") (pinfunction "B3_15") (pintype "unspecified"))
    )
    (net (code "108") (name "Net-(MCP5-B4)") (class "Default")
      (node (ref "AB5") (pin "10") (pinfunction "10_10") (pintype "input"))
      (node (ref "MCP5") (pin "14") (pinfunction "B4_14") (pintype "unspecified"))
    )
    (net (code "109") (name "Net-(MCP5-B5)") (class "Default")
      (node (ref "AB5") (pin "12") (pinfunction "12_12") (pintype "input"))
      (node (ref "MCP5") (pin "13") (pinfunction "B5_13") (pintype "unspecified"))
    )
    (net (code "110") (name "Net-(MCP5-B6)") (class "Default")
      (node (ref "AB5") (pin "14") (pinfunction "14_14") (pintype "input"))
      (node (ref "MCP5") (pin "12") (pinfunction "B6_12") (pintype "unspecified"))
    )
    (net (code "111") (name "Net-(MCP5-B7)") (class "Default")
      (node (ref "AB5") (pin "16") (pinfunction "16_16") (pintype "input"))
      (node (ref "MCP5") (pin "11") (pinfunction "B7_11") (pintype "unspecified"))
    )
    (net (code "112") (name "Net-(MCP5-ITA)") (class "Default")
      (node (ref "INTAB") (pin "11") (pinfunction "11_11") (pintype "input"))
      (node (ref "MCP5") (pin "29") (pinfunction "ITA_29") (pintype "unspecified"))
    )
    (net (code "113") (name "Net-(MCP5-ITB)") (class "Default")
      (node (ref "INTAB") (pin "12") (pinfunction "12_12") (pintype "input"))
      (node (ref "MCP5") (pin "19") (pinfunction "ITB_19") (pintype "unspecified"))
    )
    (net (code "114") (name "Net-(MCP6-A0)") (class "Default")
      (node (ref "AB6") (pin "1") (pinfunction "1_1") (pintype "input"))
      (node (ref "MCP6") (pin "28") (pinfunction "A0_28") (pintype "unspecified"))
    )
    (net (code "115") (name "Net-(MCP6-A1)") (class "Default")
      (node (ref "AB6") (pin "3") (pinfunction "3_3") (pintype "input"))
      (node (ref "MCP6") (pin "27") (pinfunction "A1_27") (pintype "unspecified"))
    )
    (net (code "116") (name "Net-(MCP6-A2)") (class "Default")
      (node (ref "AB6") (pin "5") (pinfunction "5_5") (pintype "input"))
      (node (ref "MCP6") (pin "26") (pinfunction "A2_26") (pintype "unspecified"))
    )
    (net (code "117") (name "Net-(MCP6-A3)") (class "Default")
      (node (ref "AB6") (pin "7") (pinfunction "7_7") (pintype "input"))
      (node (ref "MCP6") (pin "25") (pinfunction "A3_25") (pintype "unspecified"))
    )
    (net (code "118") (name "Net-(MCP6-A4)") (class "Default")
      (node (ref "AB6") (pin "9") (pinfunction "9_9") (pintype "input"))
      (node (ref "MCP6") (pin "24") (pinfunction "A4_24") (pintype "unspecified"))
    )
    (net (code "119") (name "Net-(MCP6-A5)") (class "Default")
      (node (ref "AB6") (pin "11") (pinfunction "11_11") (pintype "input"))
      (node (ref "MCP6") (pin "23") (pinfunction "A5_23") (pintype "unspecified"))
    )
    (net (code "120") (name "Net-(MCP6-A6)") (class "Default")
      (node (ref "AB6") (pin "13") (pinfunction "13_13") (pintype "input"))
      (node (ref "MCP6") (pin "22") (pinfunction "A6_22") (pintype "unspecified"))
    )
    (net (code "121") (name "Net-(MCP6-A7)") (class "Default")
      (node (ref "AB6") (pin "15") (pinfunction "15_15") (pintype "input"))
      (node (ref "MCP6") (pin "21") (pinfunction "A7_21") (pintype "unspecified"))
    )
    (net (code "122") (name "Net-(MCP6-B0)") (class "Default")
      (node (ref "AB6") (pin "2") (pinfunction "2_2") (pintype "input"))
      (node (ref "MCP6") (pin "18") (pinfunction "B0_18") (pintype "unspecified"))
    )
    (net (code "123") (name "Net-(MCP6-B1)") (class "Default")
      (node (ref "AB6") (pin "4") (pinfunction "4_4") (pintype "input"))
      (node (ref "MCP6") (pin "17") (pinfunction "B1_17") (pintype "unspecified"))
    )
    (net (code "124") (name "Net-(MCP6-B2)") (class "Default")
      (node (ref "AB6") (pin "6") (pinfunction "6_6") (pintype "input"))
      (node (ref "MCP6") (pin "16") (pinfunction "B2_16") (pintype "unspecified"))
    )
    (net (code "125") (name "Net-(MCP6-B3)") (class "Default")
      (node (ref "AB6") (pin "8") (pinfunction "8_8") (pintype "input"))
      (node (ref "MCP6") (pin "15") (pinfunction "B3_15") (pintype "unspecified"))
    )
    (net (code "126") (name "Net-(MCP6-B4)") (class "Default")
      (node (ref "AB6") (pin "10") (pinfunction "10_10") (pintype "input"))
      (node (ref "MCP6") (pin "14") (pinfunction "B4_14") (pintype "unspecified"))
    )
    (net (code "127") (name "Net-(MCP6-B5)") (class "Default")
      (node (ref "AB6") (pin "12") (pinfunction "12_12") (pintype "input"))
      (node (ref "MCP6") (pin "13") (pinfunction "B5_13") (pintype "unspecified"))
    )
    (net (code "128") (name "Net-(MCP6-B6)") (class "Default")
      (node (ref "AB6") (pin "14") (pinfunction "14_14") (pintype "input"))
      (node (ref "MCP6") (pin "12") (pinfunction "B6_12") (pintype "unspecified"))
    )
    (net (code "129") (name "Net-(MCP6-B7)") (class "Default")
      (node (ref "AB6") (pin "16") (pinfunction "16_16") (pintype "input"))
      (node (ref "MCP6") (pin "11") (pinfunction "B7_11") (pintype "unspecified"))
    )
    (net (code "130") (name "Net-(MCP6-ITA)") (class "Default")
      (node (ref "INTAB") (pin "13") (pinfunction "13_13") (pintype "input"))
      (node (ref "MCP6") (pin "29") (pinfunction "ITA_29") (pintype "unspecified"))
    )
    (net (code "131") (name "Net-(MCP6-ITB)") (class "Default")
      (node (ref "INTAB") (pin "14") (pinfunction "14_14") (pintype "input"))
      (node (ref "MCP6") (pin "19") (pinfunction "ITB_19") (pintype "unspecified"))
    )
    (net (code "132") (name "Net-(MCP7-A0)") (class "Default")
      (node (ref "AB7") (pin "1") (pinfunction "1_1") (pintype "input"))
      (node (ref "MCP7") (pin "28") (pinfunction "A0_28") (pintype "unspecified"))
    )
    (net (code "133") (name "Net-(MCP7-A1)") (class "Default")
      (node (ref "AB7") (pin "3") (pinfunction "3_3") (pintype "input"))
      (node (ref "MCP7") (pin "27") (pinfunction "A1_27") (pintype "unspecified"))
    )
    (net (code "134") (name "Net-(MCP7-A2)") (class "Default")
      (node (ref "AB7") (pin "5") (pinfunction "5_5") (pintype "input"))
      (node (ref "MCP7") (pin "26") (pinfunction "A2_26") (pintype "unspecified"))
    )
    (net (code "135") (name "Net-(MCP7-A3)") (class "Default")
      (node (ref "AB7") (pin "7") (pinfunction "7_7") (pintype "input"))
      (node (ref "MCP7") (pin "25") (pinfunction "A3_25") (pintype "unspecified"))
    )
    (net (code "136") (name "Net-(MCP7-A4)") (class "Default")
      (node (ref "AB7") (pin "9") (pinfunction "9_9") (pintype "input"))
      (node (ref "MCP7") (pin "24") (pinfunction "A4_24") (pintype "unspecified"))
    )
    (net (code "137") (name "Net-(MCP7-A5)") (class "Default")
      (node (ref "AB7") (pin "11") (pinfunction "11_11") (pintype "input"))
      (node (ref "MCP7") (pin "23") (pinfunction "A5_23") (pintype "unspecified"))
    )
    (net (code "138") (name "Net-(MCP7-A6)") (class "Default")
      (node (ref "AB7") (pin "13") (pinfunction "13_13") (pintype "input"))
      (node (ref "MCP7") (pin "22") (pinfunction "A6_22") (pintype "unspecified"))
    )
    (net (code "139") (name "Net-(MCP7-A7)") (class "Default")
      (node (ref "AB7") (pin "15") (pinfunction "15_15") (pintype "input"))
      (node (ref "MCP7") (pin "21") (pinfunction "A7_21") (pintype "unspecified"))
    )
    (net (code "140") (name "Net-(MCP7-B0)") (class "Default")
      (node (ref "AB7") (pin "2") (pinfunction "2_2") (pintype "input"))
      (node (ref "MCP7") (pin "18") (pinfunction "B0_18") (pintype "unspecified"))
    )
    (net (code "141") (name "Net-(MCP7-B1)") (class "Default")
      (node (ref "AB7") (pin "4") (pinfunction "4_4") (pintype "input"))
      (node (ref "MCP7") (pin "17") (pinfunction "B1_17") (pintype "unspecified"))
    )
    (net (code "142") (name "Net-(MCP7-B2)") (class "Default")
      (node (ref "AB7") (pin "6") (pinfunction "6_6") (pintype "input"))
      (node (ref "MCP7") (pin "16") (pinfunction "B2_16") (pintype "unspecified"))
    )
    (net (code "143") (name "Net-(MCP7-B3)") (class "Default")
      (node (ref "AB7") (pin "8") (pinfunction "8_8") (pintype "input"))
      (node (ref "MCP7") (pin "15") (pinfunction "B3_15") (pintype "unspecified"))
    )
    (net (code "144") (name "Net-(MCP7-B4)") (class "Default")
      (node (ref "AB7") (pin "10") (pinfunction "10_10") (pintype "input"))
      (node (ref "MCP7") (pin "14") (pinfunction "B4_14") (pintype "unspecified"))
    )
    (net (code "145") (name "Net-(MCP7-B5)") (class "Default")
      (node (ref "AB7") (pin "12") (pinfunction "12_12") (pintype "input"))
      (node (ref "MCP7") (pin "13") (pinfunction "B5_13") (pintype "unspecified"))
    )
    (net (code "146") (name "Net-(MCP7-B6)") (class "Default")
      (node (ref "AB7") (pin "14") (pinfunction "14_14") (pintype "input"))
      (node (ref "MCP7") (pin "12") (pinfunction "B6_12") (pintype "unspecified"))
    )
    (net (code "147") (name "Net-(MCP7-B7)") (class "Default")
      (node (ref "AB7") (pin "16") (pinfunction "16_16") (pintype "input"))
      (node (ref "MCP7") (pin "11") (pinfunction "B7_11") (pintype "unspecified"))
    )
    (net (code "148") (name "Net-(MCP7-ITA)") (class "Default")
      (node (ref "INTAB") (pin "15") (pinfunction "15_15") (pintype "input"))
      (node (ref "MCP7") (pin "29") (pinfunction "ITA_29") (pintype "unspecified"))
    )
    (net (code "149") (name "Net-(MCP7-ITB)") (class "Default")
      (node (ref "INTAB") (pin "16") (pinfunction "16_16") (pintype "input"))
      (node (ref "MCP7") (pin "19") (pinfunction "ITB_19") (pintype "unspecified"))
    )
    (net (code "150") (name "unconnected-(MCP0-NC{slash}CS-Pad6)") (class "Default")
      (node (ref "MCP0") (pin "6") (pinfunction "NC/CS_6") (pintype "unspecified"))
    )
    (net (code "151") (name "unconnected-(MCP0-NC{slash}SO-Pad5)") (class "Default")
      (node (ref "MCP0") (pin "5") (pinfunction "NC/SO_5") (pintype "unspecified"))
    )
    (net (code "152") (name "unconnected-(MCP1-NC{slash}CS-Pad6)") (class "Default")
      (node (ref "MCP1") (pin "6") (pinfunction "NC/CS_6") (pintype "unspecified"))
    )
    (net (code "153") (name "unconnected-(MCP1-NC{slash}SO-Pad5)") (class "Default")
      (node (ref "MCP1") (pin "5") (pinfunction "NC/SO_5") (pintype "unspecified"))
    )
    (net (code "154") (name "unconnected-(MCP2-NC{slash}CS-Pad6)") (class "Default")
      (node (ref "MCP2") (pin "6") (pinfunction "NC/CS_6") (pintype "unspecified"))
    )
    (net (code "155") (name "unconnected-(MCP2-NC{slash}SO-Pad5)") (class "Default")
      (node (ref "MCP2") (pin "5") (pinfunction "NC/SO_5") (pintype "unspecified"))
    )
    (net (code "156") (name "unconnected-(MCP3-NC{slash}CS-Pad6)") (class "Default")
      (node (ref "MCP3") (pin "6") (pinfunction "NC/CS_6") (pintype "unspecified"))
    )
    (net (code "157") (name "unconnected-(MCP3-NC{slash}SO-Pad5)") (class "Default")
      (node (ref "MCP3") (pin "5") (pinfunction "NC/SO_5") (pintype "unspecified"))
    )
    (net (code "158") (name "unconnected-(MCP4-NC{slash}CS-Pad6)") (class "Default")
      (node (ref "MCP4") (pin "6") (pinfunction "NC/CS_6") (pintype "unspecified"))
    )
    (net (code "159") (name "unconnected-(MCP4-NC{slash}SO-Pad5)") (class "Default")
      (node (ref "MCP4") (pin "5") (pinfunction "NC/SO_5") (pintype "unspecified"))
    )
    (net (code "160") (name "unconnected-(MCP5-NC{slash}CS-Pad6)") (class "Default")
      (node (ref "MCP5") (pin "6") (pinfunction "NC/CS_6") (pintype "unspecified"))
    )
    (net (code "161") (name "unconnected-(MCP5-NC{slash}SO-Pad5)") (class "Default")
      (node (ref "MCP5") (pin "5") (pinfunction "NC/SO_5") (pintype "unspecified"))
    )
    (net (code "162") (name "unconnected-(MCP6-NC{slash}CS-Pad6)") (class "Default")
      (node (ref "MCP6") (pin "6") (pinfunction "NC/CS_6") (pintype "unspecified"))
    )
    (net (code "163") (name "unconnected-(MCP6-NC{slash}SO-Pad5)") (class "Default")
      (node (ref "MCP6") (pin "5") (pinfunction "NC/SO_5") (pintype "unspecified"))
    )
    (net (code "164") (name "unconnected-(MCP7-NC{slash}CS-Pad6)") (class "Default")
      (node (ref "MCP7") (pin "6") (pinfunction "NC/CS_6") (pintype "unspecified"))
    )
    (net (code "165") (name "unconnected-(MCP7-NC{slash}SO-Pad5)") (class "Default")
      (node (ref "MCP7") (pin "5") (pinfunction "NC/SO_5") (pintype "unspecified"))
    )
  )
)
